# 6566_adapter_2.net
KiCad netlist of a schematic drawn in EAGLE
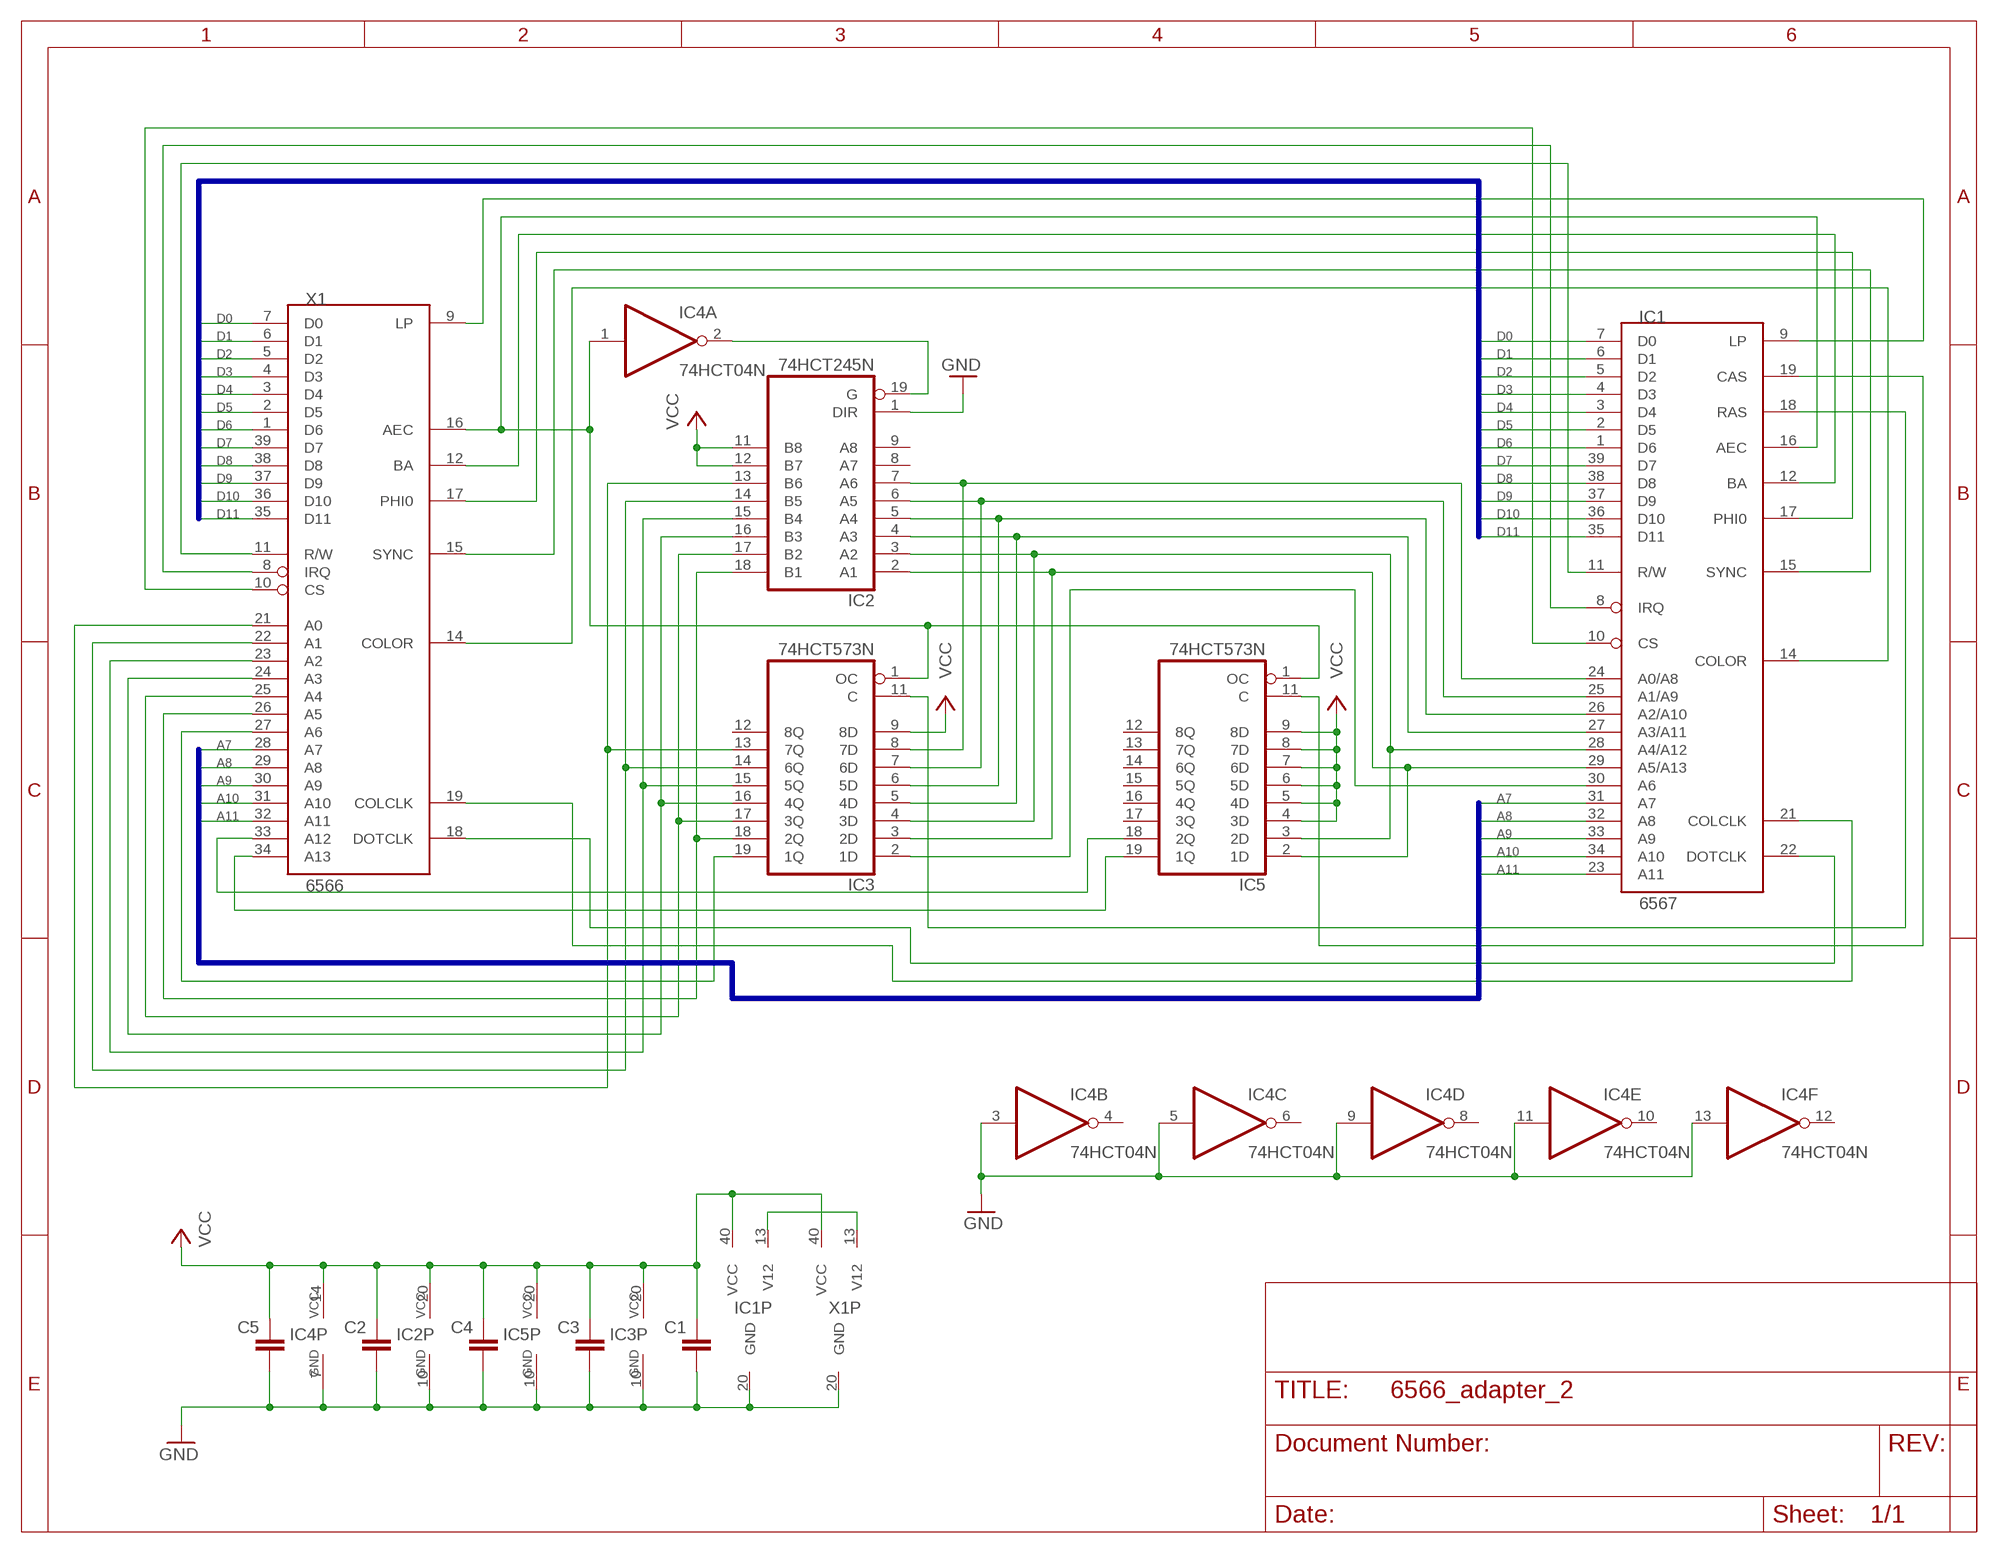
[diagram p0: schematic, sheet 1]

(export (version "E")
  (design (tool "Eeschema 10.0.6"))
  (components
    (comp (ref "C1")
      (value "C-EU025-025X050")
      (footprint "eagle-import:C025-025X050")
      (libsource (lib "eagle-import") (part "C-EU025-025X050"))
    )
    (comp (ref "C2")
      (value "C-EU025-025X050")
      (footprint "eagle-import:C025-025X050")
      (libsource (lib "eagle-import") (part "C-EU025-025X050"))
    )
    (comp (ref "C3")
      (value "C-EU025-025X050")
      (footprint "eagle-import:C025-025X050")
      (libsource (lib "eagle-import") (part "C-EU025-025X050"))
    )
    (comp (ref "C4")
      (value "C-EU025-025X050")
      (footprint "eagle-import:C025-025X050")
      (libsource (lib "eagle-import") (part "C-EU025-025X050"))
    )
    (comp (ref "C5")
      (value "C-EU025-025X050")
      (footprint "eagle-import:C025-025X050")
      (libsource (lib "eagle-import") (part "C-EU025-025X050"))
    )
    (comp (ref "IC1")
      (value "6567")
      (footprint "eagle-import:DIP40")
      (libsource (lib "eagle-import") (part "6569"))
    )
    (comp (ref "IC2")
      (value "74HCT245N")
      (footprint "eagle-import:DIL20")
      (libsource (lib "eagle-import") (part "74245NHCT"))
    )
    (comp (ref "IC3")
      (value "74HCT573N")
      (footprint "eagle-import:DIL20")
      (libsource (lib "eagle-import") (part "74573NHCT"))
    )
    (comp (ref "IC4")
      (value "74HCT04N")
      (footprint "eagle-import:DIL14")
      (libsource (lib "eagle-import") (part "7404NHCT"))
    )
    (comp (ref "IC5")
      (value "74HCT573N")
      (footprint "eagle-import:DIL20")
      (libsource (lib "eagle-import") (part "74573NHCT"))
    )
    (comp (ref "X1")
      (value "6566")
      (footprint "eagle-import:DIL40")
      (libsource (lib "eagle-import") (part "6566"))
    )
  )
  (nets
    (net (code "1") (name "/A7") (class "Default")
      (node (ref "IC1") (pin "31") (pinfunction "A7_31") (pintype "bidirectional"))
      (node (ref "X1") (pin "28") (pinfunction "A7_28") (pintype "bidirectional"))
    )
    (net (code "2") (name "/A8") (class "Default")
      (node (ref "IC1") (pin "32") (pinfunction "A8_32") (pintype "input"))
      (node (ref "X1") (pin "29") (pinfunction "A8_29") (pintype "input"))
    )
    (net (code "3") (name "/A9") (class "Default")
      (node (ref "IC1") (pin "33") (pinfunction "A9_33") (pintype "input"))
      (node (ref "X1") (pin "30") (pinfunction "A9_30") (pintype "input"))
    )
    (net (code "4") (name "/A10") (class "Default")
      (node (ref "IC1") (pin "34") (pinfunction "A10_34") (pintype "input"))
      (node (ref "X1") (pin "31") (pinfunction "A10_31") (pintype "input"))
    )
    (net (code "5") (name "/A11") (class "Default")
      (node (ref "IC1") (pin "23") (pinfunction "A11_23") (pintype "input"))
      (node (ref "X1") (pin "32") (pinfunction "A11_32") (pintype "input"))
    )
    (net (code "6") (name "/D0") (class "Default")
      (node (ref "IC1") (pin "7") (pinfunction "D0_7") (pintype "tri_state"))
      (node (ref "X1") (pin "7") (pinfunction "D0_7") (pintype "tri_state"))
    )
    (net (code "7") (name "/D1") (class "Default")
      (node (ref "IC1") (pin "6") (pinfunction "D1_6") (pintype "tri_state"))
      (node (ref "X1") (pin "6") (pinfunction "D1_6") (pintype "tri_state"))
    )
    (net (code "8") (name "/D2") (class "Default")
      (node (ref "IC1") (pin "5") (pinfunction "D2_5") (pintype "tri_state"))
      (node (ref "X1") (pin "5") (pinfunction "D2_5") (pintype "tri_state"))
    )
    (net (code "9") (name "/D3") (class "Default")
      (node (ref "IC1") (pin "4") (pinfunction "D3_4") (pintype "tri_state"))
      (node (ref "X1") (pin "4") (pinfunction "D3_4") (pintype "tri_state"))
    )
    (net (code "10") (name "/D4") (class "Default")
      (node (ref "IC1") (pin "3") (pinfunction "D4_3") (pintype "tri_state"))
      (node (ref "X1") (pin "3") (pinfunction "D4_3") (pintype "tri_state"))
    )
    (net (code "11") (name "/D5") (class "Default")
      (node (ref "IC1") (pin "2") (pinfunction "D5_2") (pintype "tri_state"))
      (node (ref "X1") (pin "2") (pinfunction "D5_2") (pintype "tri_state"))
    )
    (net (code "12") (name "/D6") (class "Default")
      (node (ref "IC1") (pin "1") (pinfunction "D6_1") (pintype "tri_state"))
      (node (ref "X1") (pin "1") (pinfunction "D6_1") (pintype "tri_state"))
    )
    (net (code "13") (name "/D7") (class "Default")
      (node (ref "IC1") (pin "39") (pinfunction "D7_39") (pintype "tri_state"))
      (node (ref "X1") (pin "39") (pinfunction "D7_39") (pintype "tri_state"))
    )
    (net (code "14") (name "/D8") (class "Default")
      (node (ref "IC1") (pin "38") (pinfunction "D8_38") (pintype "tri_state"))
      (node (ref "X1") (pin "38") (pinfunction "D8_38") (pintype "tri_state"))
    )
    (net (code "15") (name "/D9") (class "Default")
      (node (ref "IC1") (pin "37") (pinfunction "D9_37") (pintype "tri_state"))
      (node (ref "X1") (pin "37") (pinfunction "D9_37") (pintype "tri_state"))
    )
    (net (code "16") (name "/D10") (class "Default")
      (node (ref "IC1") (pin "36") (pinfunction "D10_36") (pintype "tri_state"))
      (node (ref "X1") (pin "36") (pinfunction "D10_36") (pintype "tri_state"))
    )
    (net (code "17") (name "/D11") (class "Default")
      (node (ref "IC1") (pin "35") (pinfunction "D11_35") (pintype "tri_state"))
      (node (ref "X1") (pin "35") (pinfunction "D11_35") (pintype "tri_state"))
    )
    (net (code "18") (name "GND") (class "Default")
      (node (ref "C1") (pin "2") (pinfunction "2_2") (pintype "passive"))
      (node (ref "C2") (pin "2") (pinfunction "2_2") (pintype "passive"))
      (node (ref "C3") (pin "2") (pinfunction "2_2") (pintype "passive"))
      (node (ref "C4") (pin "2") (pinfunction "2_2") (pintype "passive"))
      (node (ref "C5") (pin "2") (pinfunction "2_2") (pintype "passive"))
      (node (ref "IC1") (pin "20") (pinfunction "GND_20") (pintype "power_in"))
      (node (ref "IC2") (pin "1") (pinfunction "DIR_1") (pintype "input"))
      (node (ref "IC2") (pin "10") (pinfunction "GND_10") (pintype "power_in"))
      (node (ref "IC3") (pin "10") (pinfunction "GND_10") (pintype "power_in"))
      (node (ref "IC4") (pin "11") (pinfunction "I_11") (pintype "input"))
      (node (ref "IC4") (pin "13") (pinfunction "I_13") (pintype "input"))
      (node (ref "IC4") (pin "3") (pinfunction "I_3") (pintype "input"))
      (node (ref "IC4") (pin "5") (pinfunction "I_5") (pintype "input"))
      (node (ref "IC4") (pin "7") (pinfunction "GND_7") (pintype "power_in"))
      (node (ref "IC4") (pin "9") (pinfunction "I_9") (pintype "input"))
      (node (ref "IC5") (pin "10") (pinfunction "GND_10") (pintype "power_in"))
      (node (ref "X1") (pin "20") (pinfunction "GND_20") (pintype "power_in"))
    )
    (net (code "19") (name "Net-(IC1A-A0{slash}A8)") (class "Default")
      (node (ref "IC1") (pin "24") (pinfunction "A0/A8_24") (pintype "bidirectional"))
      (node (ref "IC2") (pin "7") (pinfunction "A6_7") (pintype "bidirectional"))
      (node (ref "IC3") (pin "8") (pinfunction "7D_8") (pintype "input"))
    )
    (net (code "20") (name "Net-(IC1A-A1{slash}A9)") (class "Default")
      (node (ref "IC1") (pin "25") (pinfunction "A1/A9_25") (pintype "bidirectional"))
      (node (ref "IC2") (pin "6") (pinfunction "A5_6") (pintype "bidirectional"))
      (node (ref "IC3") (pin "7") (pinfunction "6D_7") (pintype "input"))
    )
    (net (code "21") (name "Net-(IC1A-A2{slash}A10)") (class "Default")
      (node (ref "IC1") (pin "26") (pinfunction "A2/A10_26") (pintype "bidirectional"))
      (node (ref "IC2") (pin "5") (pinfunction "A4_5") (pintype "bidirectional"))
      (node (ref "IC3") (pin "6") (pinfunction "5D_6") (pintype "input"))
    )
    (net (code "22") (name "Net-(IC1A-A3{slash}A11)") (class "Default")
      (node (ref "IC1") (pin "27") (pinfunction "A3/A11_27") (pintype "bidirectional"))
      (node (ref "IC2") (pin "4") (pinfunction "A3_4") (pintype "bidirectional"))
      (node (ref "IC3") (pin "5") (pinfunction "4D_5") (pintype "input"))
    )
    (net (code "23") (name "Net-(IC1A-A4{slash}A12)") (class "Default")
      (node (ref "IC1") (pin "28") (pinfunction "A4/A12_28") (pintype "bidirectional"))
      (node (ref "IC2") (pin "3") (pinfunction "A2_3") (pintype "bidirectional"))
      (node (ref "IC3") (pin "4") (pinfunction "3D_4") (pintype "input"))
      (node (ref "IC5") (pin "3") (pinfunction "2D_3") (pintype "input"))
    )
    (net (code "24") (name "Net-(IC1A-A5{slash}A13)") (class "Default")
      (node (ref "IC1") (pin "29") (pinfunction "A5/A13_29") (pintype "bidirectional"))
      (node (ref "IC2") (pin "2") (pinfunction "A1_2") (pintype "bidirectional"))
      (node (ref "IC3") (pin "3") (pinfunction "2D_3") (pintype "input"))
      (node (ref "IC5") (pin "2") (pinfunction "1D_2") (pintype "input"))
    )
    (net (code "25") (name "Net-(IC1A-A6)") (class "Default")
      (node (ref "IC1") (pin "30") (pinfunction "A6_30") (pintype "bidirectional"))
      (node (ref "IC3") (pin "2") (pinfunction "1D_2") (pintype "input"))
    )
    (net (code "26") (name "Net-(IC1A-AEC)") (class "Default")
      (node (ref "IC1") (pin "16") (pinfunction "AEC_16") (pintype "output"))
      (node (ref "IC3") (pin "1") (pinfunction "OC_1") (pintype "input"))
      (node (ref "IC4") (pin "1") (pinfunction "I_1") (pintype "input"))
      (node (ref "IC5") (pin "1") (pinfunction "OC_1") (pintype "input"))
      (node (ref "X1") (pin "16") (pinfunction "AEC_16") (pintype "output"))
    )
    (net (code "27") (name "Net-(IC1A-BA)") (class "Default")
      (node (ref "IC1") (pin "12") (pinfunction "BA_12") (pintype "output"))
      (node (ref "X1") (pin "12") (pinfunction "BA_12") (pintype "output"))
    )
    (net (code "28") (name "Net-(IC1A-CAS)") (class "Default")
      (node (ref "IC1") (pin "19") (pinfunction "CAS_19") (pintype "output"))
      (node (ref "IC5") (pin "11") (pinfunction "C_11") (pintype "input"))
    )
    (net (code "29") (name "Net-(IC1A-COLCLK)") (class "Default")
      (node (ref "IC1") (pin "21") (pinfunction "COLCLK_21") (pintype "input"))
      (node (ref "X1") (pin "19") (pinfunction "COLCLK_19") (pintype "input"))
    )
    (net (code "30") (name "Net-(IC1A-COLOR)") (class "Default")
      (node (ref "IC1") (pin "14") (pinfunction "COLOR_14") (pintype "output"))
      (node (ref "X1") (pin "14") (pinfunction "COLOR_14") (pintype "output"))
    )
    (net (code "31") (name "Net-(IC1A-CS)") (class "Default")
      (node (ref "IC1") (pin "10") (pinfunction "CS_10") (pintype "input"))
      (node (ref "X1") (pin "10") (pinfunction "CS_10") (pintype "input"))
    )
    (net (code "32") (name "Net-(IC1A-DOTCLK)") (class "Default")
      (node (ref "IC1") (pin "22") (pinfunction "DOTCLK_22") (pintype "input"))
      (node (ref "X1") (pin "18") (pinfunction "DOTCLK_18") (pintype "input"))
    )
    (net (code "33") (name "Net-(IC1A-IRQ)") (class "Default")
      (node (ref "IC1") (pin "8") (pinfunction "IRQ_8") (pintype "open_collector"))
      (node (ref "X1") (pin "8") (pinfunction "IRQ_8") (pintype "open_collector"))
    )
    (net (code "34") (name "Net-(IC1A-LP)") (class "Default")
      (node (ref "IC1") (pin "9") (pinfunction "LP_9") (pintype "input"))
      (node (ref "X1") (pin "9") (pinfunction "LP_9") (pintype "input"))
    )
    (net (code "35") (name "Net-(IC1A-PHI0)") (class "Default")
      (node (ref "IC1") (pin "17") (pinfunction "PHI0_17") (pintype "output"))
      (node (ref "X1") (pin "17") (pinfunction "PHI0_17") (pintype "output"))
    )
    (net (code "36") (name "Net-(IC1A-RAS)") (class "Default")
      (node (ref "IC1") (pin "18") (pinfunction "RAS_18") (pintype "output"))
      (node (ref "IC3") (pin "11") (pinfunction "C_11") (pintype "input"))
    )
    (net (code "37") (name "Net-(IC1A-R{slash}W)") (class "Default")
      (node (ref "IC1") (pin "11") (pinfunction "R/W_11") (pintype "input"))
      (node (ref "X1") (pin "11") (pinfunction "R/W_11") (pintype "input"))
    )
    (net (code "38") (name "Net-(IC1A-SYNC)") (class "Default")
      (node (ref "IC1") (pin "15") (pinfunction "SYNC_15") (pintype "output"))
      (node (ref "X1") (pin "15") (pinfunction "SYNC_15") (pintype "output"))
    )
    (net (code "39") (name "Net-(IC1B-V12)") (class "Default")
      (node (ref "IC1") (pin "13") (pinfunction "V12_13") (pintype "power_in"))
      (node (ref "X1") (pin "13") (pinfunction "V12_13") (pintype "power_in"))
    )
    (net (code "40") (name "Net-(IC2A-B1)") (class "Default")
      (node (ref "IC2") (pin "18") (pinfunction "B1_18") (pintype "bidirectional"))
      (node (ref "IC3") (pin "18") (pinfunction "2Q_18") (pintype "tri_state"))
      (node (ref "X1") (pin "26") (pinfunction "A5_26") (pintype "bidirectional"))
    )
    (net (code "41") (name "Net-(IC2A-B2)") (class "Default")
      (node (ref "IC2") (pin "17") (pinfunction "B2_17") (pintype "bidirectional"))
      (node (ref "IC3") (pin "17") (pinfunction "3Q_17") (pintype "tri_state"))
      (node (ref "X1") (pin "25") (pinfunction "A4_25") (pintype "bidirectional"))
    )
    (net (code "42") (name "Net-(IC2A-B3)") (class "Default")
      (node (ref "IC2") (pin "16") (pinfunction "B3_16") (pintype "bidirectional"))
      (node (ref "IC3") (pin "16") (pinfunction "4Q_16") (pintype "tri_state"))
      (node (ref "X1") (pin "24") (pinfunction "A3_24") (pintype "bidirectional"))
    )
    (net (code "43") (name "Net-(IC2A-B4)") (class "Default")
      (node (ref "IC2") (pin "15") (pinfunction "B4_15") (pintype "bidirectional"))
      (node (ref "IC3") (pin "15") (pinfunction "5Q_15") (pintype "tri_state"))
      (node (ref "X1") (pin "23") (pinfunction "A2_23") (pintype "bidirectional"))
    )
    (net (code "44") (name "Net-(IC2A-B5)") (class "Default")
      (node (ref "IC2") (pin "14") (pinfunction "B5_14") (pintype "bidirectional"))
      (node (ref "IC3") (pin "14") (pinfunction "6Q_14") (pintype "tri_state"))
      (node (ref "X1") (pin "22") (pinfunction "A1_22") (pintype "bidirectional"))
    )
    (net (code "45") (name "Net-(IC2A-B6)") (class "Default")
      (node (ref "IC2") (pin "13") (pinfunction "B6_13") (pintype "bidirectional"))
      (node (ref "IC3") (pin "13") (pinfunction "7Q_13") (pintype "tri_state"))
      (node (ref "X1") (pin "21") (pinfunction "A0_21") (pintype "bidirectional"))
    )
    (net (code "46") (name "Net-(IC2A-G)") (class "Default")
      (node (ref "IC2") (pin "19") (pinfunction "G_19") (pintype "input"))
      (node (ref "IC4") (pin "2") (pinfunction "O_2") (pintype "output"))
    )
    (net (code "47") (name "Net-(IC3A-1Q)") (class "Default")
      (node (ref "IC3") (pin "19") (pinfunction "1Q_19") (pintype "tri_state"))
      (node (ref "X1") (pin "27") (pinfunction "A6_27") (pintype "bidirectional"))
    )
    (net (code "48") (name "Net-(IC5A-1Q)") (class "Default")
      (node (ref "IC5") (pin "19") (pinfunction "1Q_19") (pintype "tri_state"))
      (node (ref "X1") (pin "34") (pinfunction "A13_34") (pintype "input"))
    )
    (net (code "49") (name "Net-(IC5A-2Q)") (class "Default")
      (node (ref "IC5") (pin "18") (pinfunction "2Q_18") (pintype "tri_state"))
      (node (ref "X1") (pin "33") (pinfunction "A12_33") (pintype "input"))
    )
    (net (code "50") (name "VCC") (class "Default")
      (node (ref "C1") (pin "1") (pinfunction "1_1") (pintype "passive"))
      (node (ref "C2") (pin "1") (pinfunction "1_1") (pintype "passive"))
      (node (ref "C3") (pin "1") (pinfunction "1_1") (pintype "passive"))
      (node (ref "C4") (pin "1") (pinfunction "1_1") (pintype "passive"))
      (node (ref "C5") (pin "1") (pinfunction "1_1") (pintype "passive"))
      (node (ref "IC1") (pin "40") (pinfunction "VCC_40") (pintype "power_in"))
      (node (ref "IC2") (pin "11") (pinfunction "B8_11") (pintype "bidirectional"))
      (node (ref "IC2") (pin "12") (pinfunction "B7_12") (pintype "bidirectional"))
      (node (ref "IC2") (pin "20") (pinfunction "VCC_20") (pintype "power_in"))
      (node (ref "IC3") (pin "20") (pinfunction "VCC_20") (pintype "power_in"))
      (node (ref "IC3") (pin "9") (pinfunction "8D_9") (pintype "input"))
      (node (ref "IC4") (pin "14") (pinfunction "VCC_14") (pintype "power_in"))
      (node (ref "IC5") (pin "20") (pinfunction "VCC_20") (pintype "power_in"))
      (node (ref "IC5") (pin "4") (pinfunction "3D_4") (pintype "input"))
      (node (ref "IC5") (pin "5") (pinfunction "4D_5") (pintype "input"))
      (node (ref "IC5") (pin "6") (pinfunction "5D_6") (pintype "input"))
      (node (ref "IC5") (pin "7") (pinfunction "6D_7") (pintype "input"))
      (node (ref "IC5") (pin "8") (pinfunction "7D_8") (pintype "input"))
      (node (ref "IC5") (pin "9") (pinfunction "8D_9") (pintype "input"))
      (node (ref "X1") (pin "40") (pinfunction "VCC_40") (pintype "power_in"))
    )
    (net (code "51") (name "unconnected-(IC2A-A7-Pad8)") (class "Default")
      (node (ref "IC2") (pin "8") (pinfunction "A7_8") (pintype "bidirectional"))
    )
    (net (code "52") (name "unconnected-(IC2A-A8-Pad9)") (class "Default")
      (node (ref "IC2") (pin "9") (pinfunction "A8_9") (pintype "bidirectional"))
    )
    (net (code "53") (name "unconnected-(IC3A-8Q-Pad12)") (class "Default")
      (node (ref "IC3") (pin "12") (pinfunction "8Q_12") (pintype "tri_state"))
    )
    (net (code "54") (name "unconnected-(IC4B-O-Pad4)") (class "Default")
      (node (ref "IC4") (pin "4") (pinfunction "O_4") (pintype "output"))
    )
    (net (code "55") (name "unconnected-(IC4C-O-Pad6)") (class "Default")
      (node (ref "IC4") (pin "6") (pinfunction "O_6") (pintype "output"))
    )
    (net (code "56") (name "unconnected-(IC4D-O-Pad8)") (class "Default")
      (node (ref "IC4") (pin "8") (pinfunction "O_8") (pintype "output"))
    )
    (net (code "57") (name "unconnected-(IC4E-O-Pad10)") (class "Default")
      (node (ref "IC4") (pin "10") (pinfunction "O_10") (pintype "output"))
    )
    (net (code "58") (name "unconnected-(IC4F-O-Pad12)") (class "Default")
      (node (ref "IC4") (pin "12") (pinfunction "O_12") (pintype "output"))
    )
    (net (code "59") (name "unconnected-(IC5A-3Q-Pad17)") (class "Default")
      (node (ref "IC5") (pin "17") (pinfunction "3Q_17") (pintype "tri_state"))
    )
    (net (code "60") (name "unconnected-(IC5A-4Q-Pad16)") (class "Default")
      (node (ref "IC5") (pin "16") (pinfunction "4Q_16") (pintype "tri_state"))
    )
    (net (code "61") (name "unconnected-(IC5A-5Q-Pad15)") (class "Default")
      (node (ref "IC5") (pin "15") (pinfunction "5Q_15") (pintype "tri_state"))
    )
    (net (code "62") (name "unconnected-(IC5A-6Q-Pad14)") (class "Default")
      (node (ref "IC5") (pin "14") (pinfunction "6Q_14") (pintype "tri_state"))
    )
    (net (code "63") (name "unconnected-(IC5A-7Q-Pad13)") (class "Default")
      (node (ref "IC5") (pin "13") (pinfunction "7Q_13") (pintype "tri_state"))
    )
    (net (code "64") (name "unconnected-(IC5A-8Q-Pad12)") (class "Default")
      (node (ref "IC5") (pin "12") (pinfunction "8Q_12") (pintype "tri_state"))
    )
  )
)
